# OLED-Pi_H.net
KiCad netlist of a schematic drawn in EAGLE
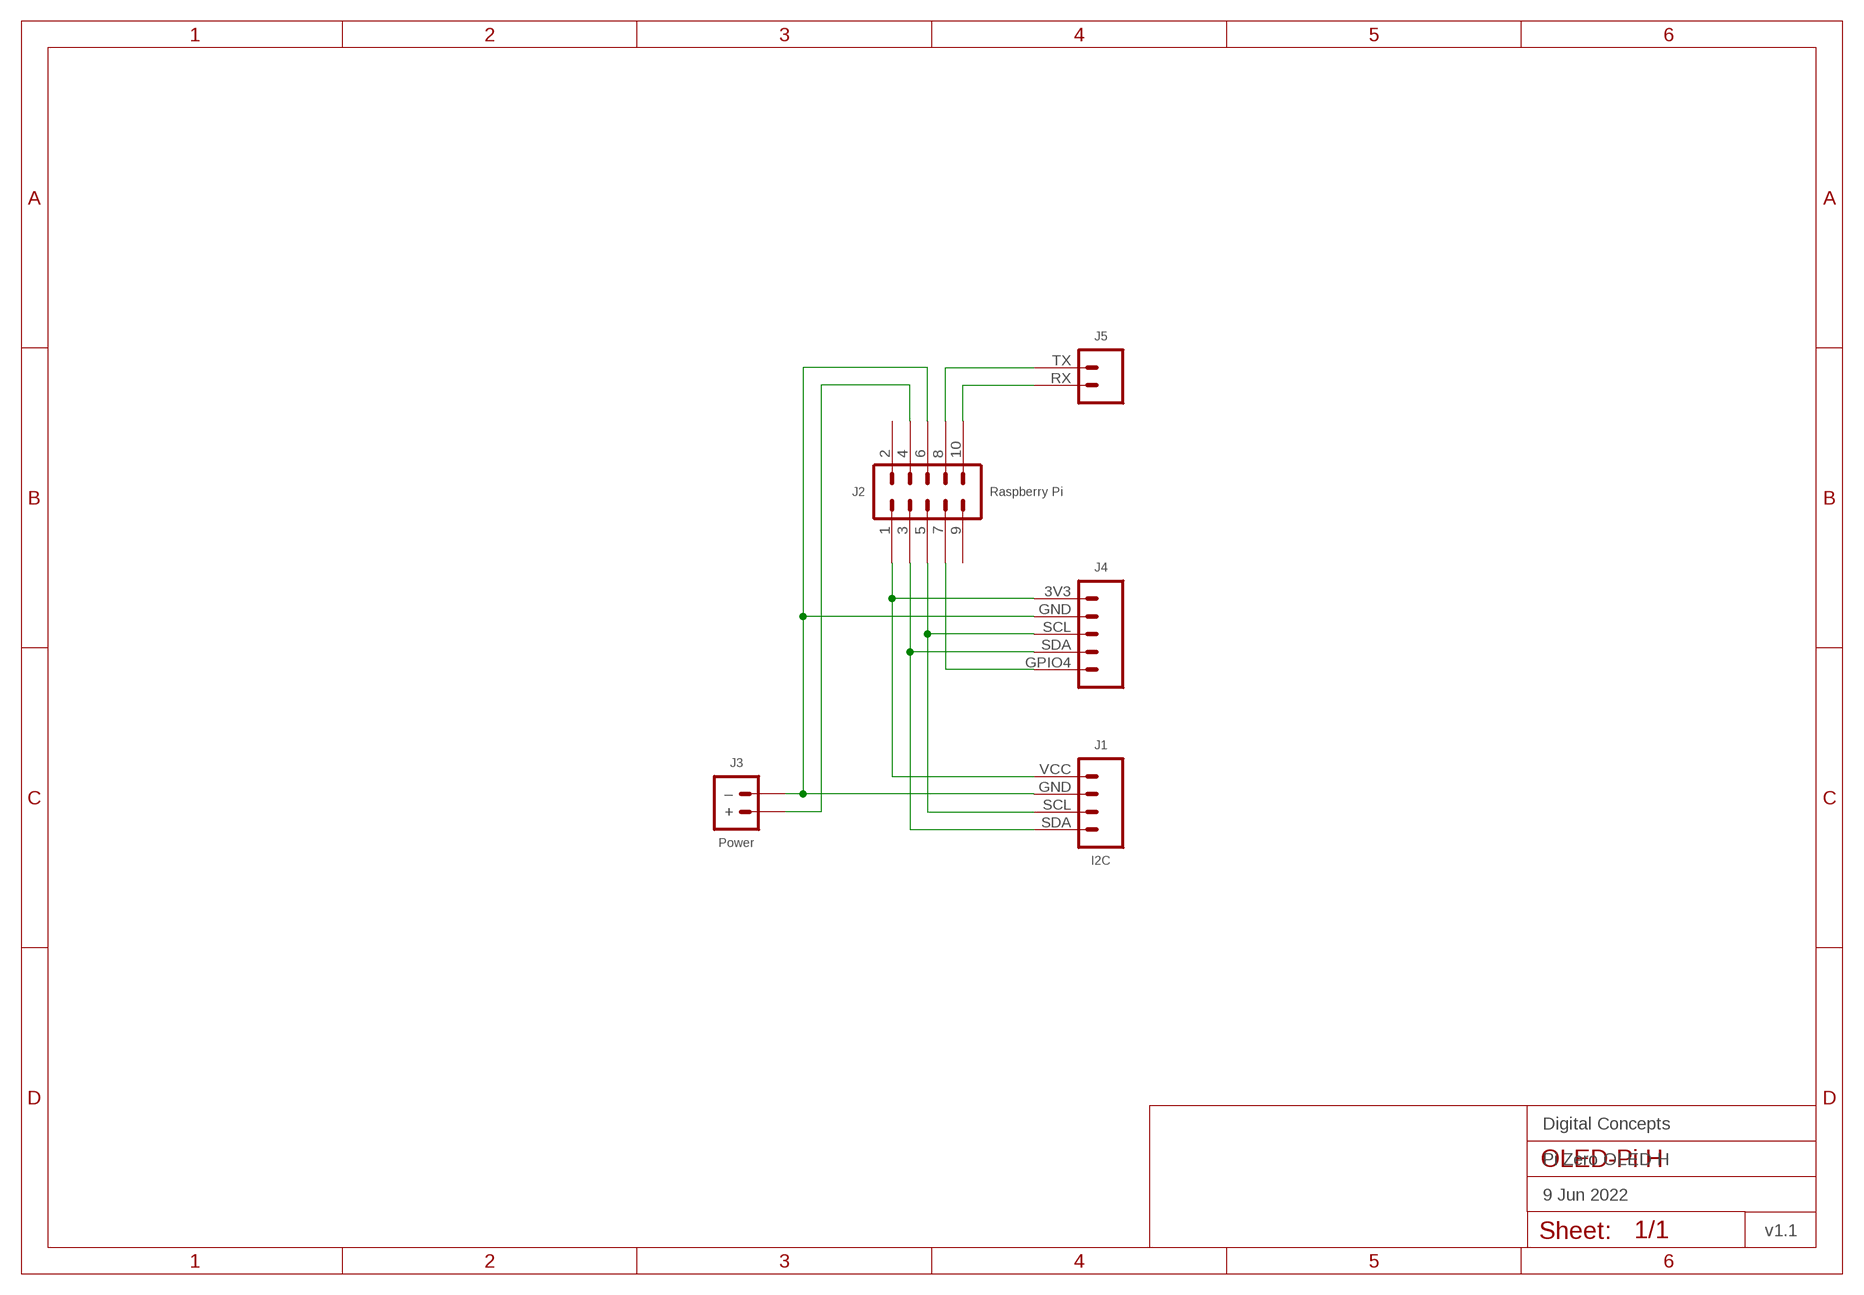
[diagram p0: schematic, sheet 1]

(export (version "E")
  (design (tool "Eeschema 10.0.6"))
  (components
    (comp (ref "J1")
      (value "I2C")
      (footprint "eagle-import:CONN_04-I2C")
      (libsource (lib "eagle-import") (part "HEADER-1X4-I2C"))
    )
    (comp (ref "J2")
      (value "Raspberry Pi")
      (footprint "eagle-import:CONN_2X5-PI-1")
      (libsource (lib "eagle-import") (part "HEADER-2X5-PI-1"))
    )
    (comp (ref "J3")
      (value "Power")
      (footprint "eagle-import:JST-PH2.0-2-HORIZONTAL-POWER")
      (libsource (lib "eagle-import") (part "JST-PH2.0-2-HORIZONTAL-POWERJST-PTH-2"))
    )
    (comp (ref "J4")
      (value "JST-PH2.0-5-HORIZONTAL-OLED-PI")
      (footprint "eagle-import:JST-PH2.0-5-HORIZONTAL-OLED-PI")
      (libsource (lib "eagle-import") (part "JST-PH2.0-5-HORIZONTAL-OLED-PI"))
    )
    (comp (ref "J5")
      (value "JST-PH2.0-2-HORIZONTAL-TX-RXJST-PTH-2")
      (footprint "eagle-import:JST-PH2.0-2-HORIZONTAL=TX-RX")
      (libsource (lib "eagle-import") (part "JST-PH2.0-2-HORIZONTAL-TX-RXJST-PTH-2"))
    )
  )
  (nets
    (net (code "1") (name "Net-(J1-1)") (class "Default")
      (node (ref "J1") (pin "VCC") (pinfunction "1_VCC") (pintype "passive"))
      (node (ref "J2") (pin "1") (pinfunction "1_1") (pintype "passive"))
      (node (ref "J4") (pin "3V3") (pinfunction "1_3V3") (pintype "passive"))
    )
    (net (code "2") (name "Net-(J1-2)") (class "Default")
      (node (ref "J1") (pin "GND") (pinfunction "2_GND") (pintype "passive"))
      (node (ref "J2") (pin "6") (pinfunction "8_6") (pintype "passive"))
      (node (ref "J3") (pin "-") (pinfunction "–_-") (pintype "power_in"))
      (node (ref "J4") (pin "GND") (pinfunction "2_GND") (pintype "passive"))
    )
    (net (code "3") (name "Net-(J1-3)") (class "Default")
      (node (ref "J1") (pin "SCL") (pinfunction "3_SCL") (pintype "passive"))
      (node (ref "J2") (pin "5") (pinfunction "3_5") (pintype "passive"))
      (node (ref "J4") (pin "SCL") (pinfunction "3_SCL") (pintype "passive"))
    )
    (net (code "4") (name "Net-(J1-4)") (class "Default")
      (node (ref "J1") (pin "SDA") (pinfunction "4_SDA") (pintype "passive"))
      (node (ref "J2") (pin "3") (pinfunction "2_3") (pintype "passive"))
      (node (ref "J4") (pin "SDA") (pinfunction "4_SDA") (pintype "passive"))
    )
    (net (code "5") (name "Net-(J2-4)") (class "Default")
      (node (ref "J2") (pin "7") (pinfunction "4_7") (pintype "passive"))
      (node (ref "J4") (pin "GPIO4") (pinfunction "5_GPIO4") (pintype "passive"))
    )
    (net (code "6") (name "Net-(J2-6)") (class "Default")
      (node (ref "J2") (pin "10") (pinfunction "6_10") (pintype "passive"))
      (node (ref "J5") (pin "RX") (pinfunction "2_RX") (pintype "passive"))
    )
    (net (code "7") (name "Net-(J2-7)") (class "Default")
      (node (ref "J2") (pin "8") (pinfunction "7_8") (pintype "passive"))
      (node (ref "J5") (pin "TX") (pinfunction "1_TX") (pintype "passive"))
    )
    (net (code "8") (name "Net-(J2-9)") (class "Default")
      (node (ref "J2") (pin "4") (pinfunction "9_4") (pintype "passive"))
      (node (ref "J3") (pin "+") (pinfunction "+_+") (pintype "power_in"))
    )
    (net (code "9") (name "unconnected-(J2-5-Pad9)") (class "Default")
      (node (ref "J2") (pin "9") (pinfunction "5_9") (pintype "passive"))
    )
    (net (code "10") (name "unconnected-(J2-10-Pad2)") (class "Default")
      (node (ref "J2") (pin "2") (pinfunction "10_2") (pintype "passive"))
    )
  )
)
